# M401.net
KiCad netlist of a schematic drawn in EAGLE
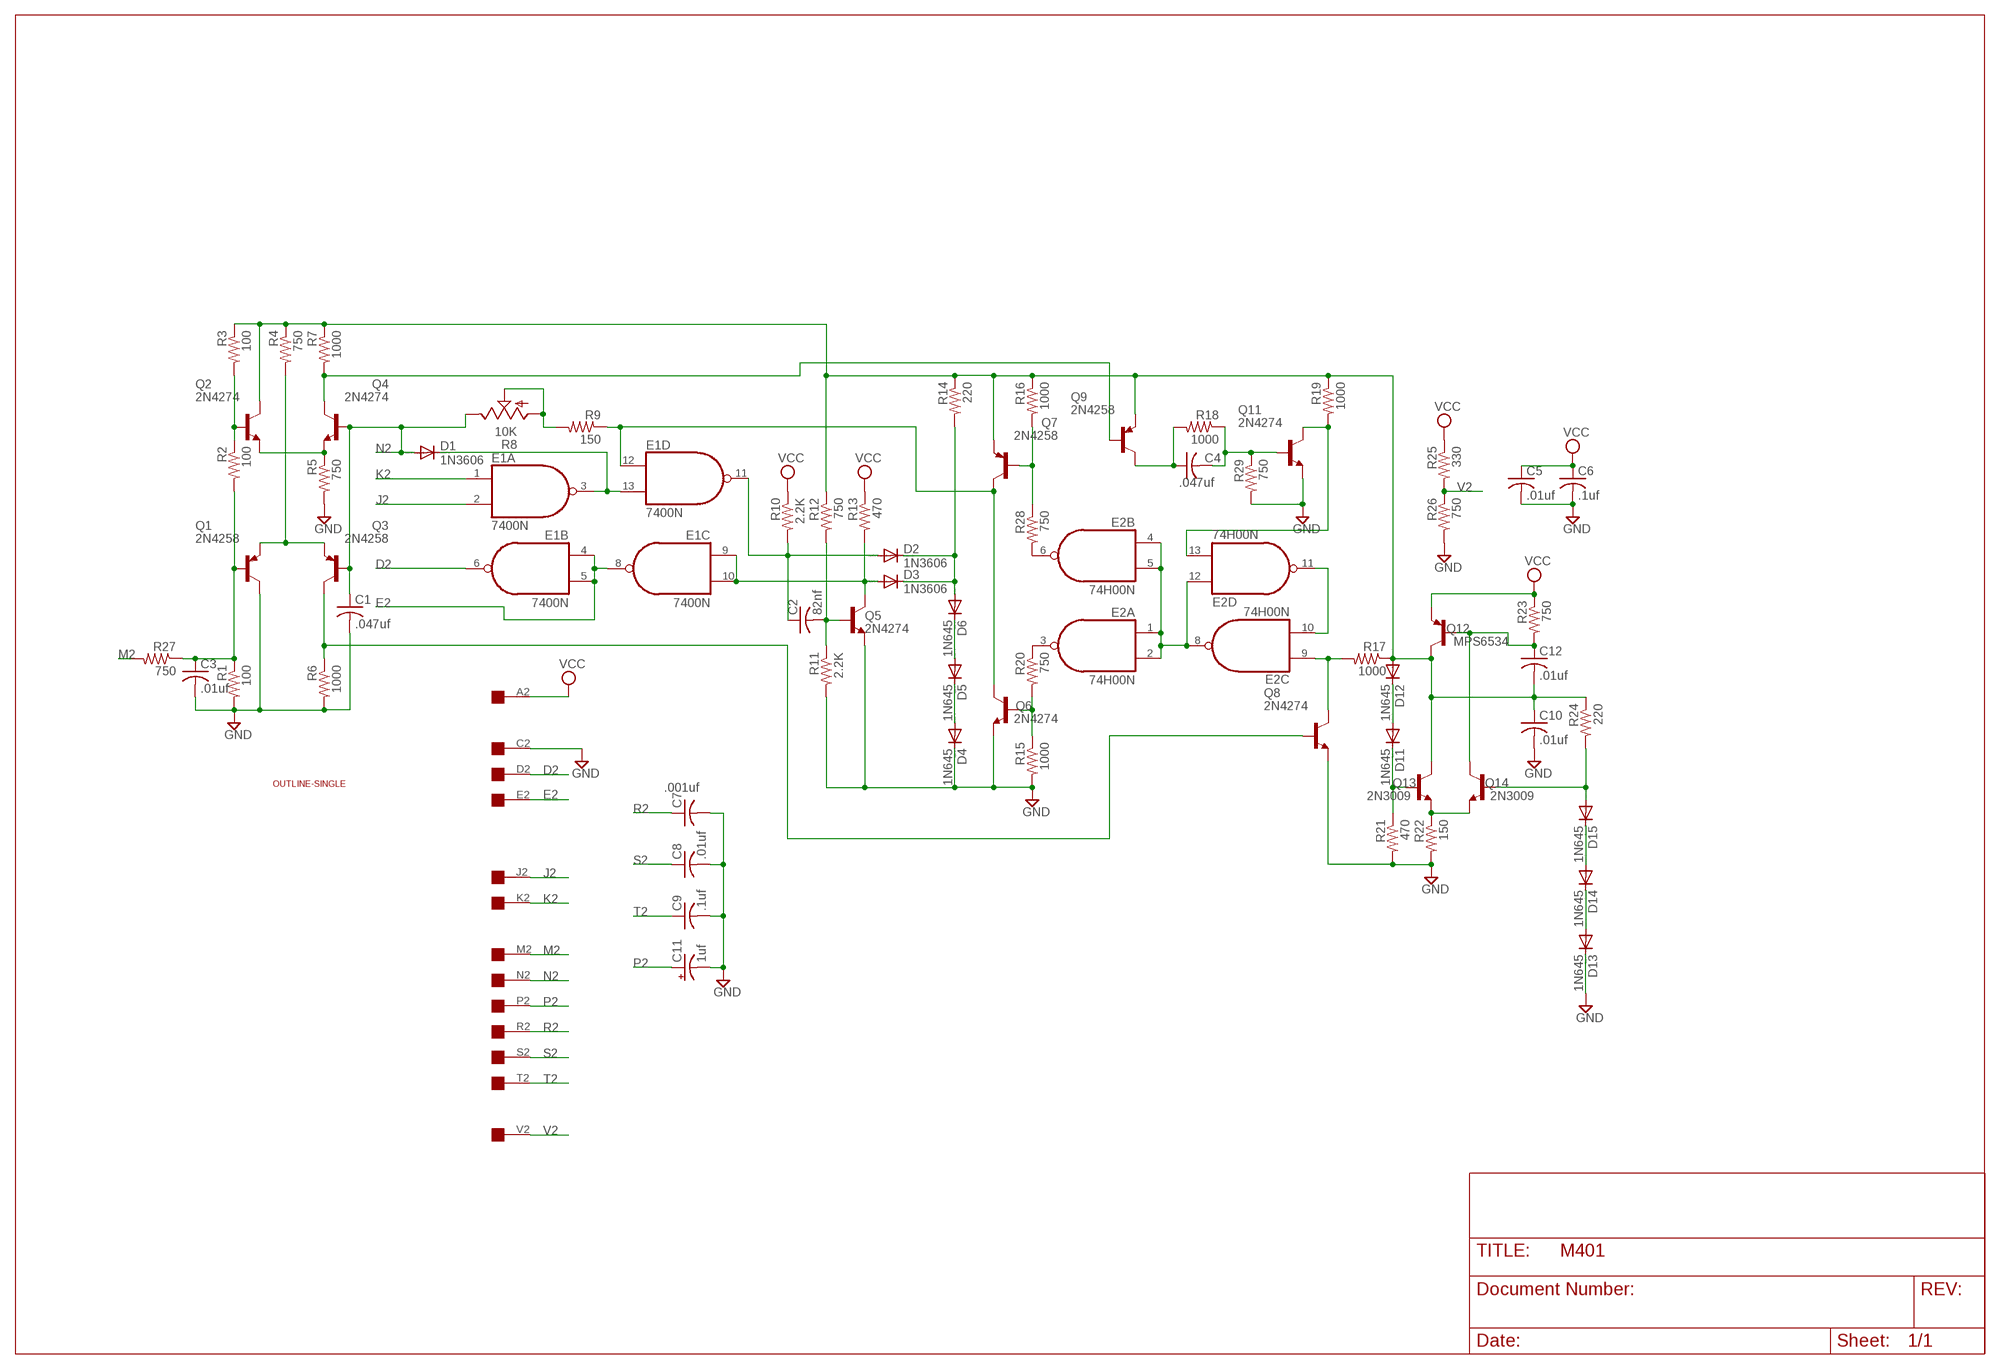
[diagram p0: schematic, sheet 1]

(export (version "E")
  (design (tool "Eeschema 10.0.6"))
  (components
    (comp (ref "C1")
      (value ".047uf")
      (footprint "eagle-import:C050-025X075")
      (libsource (lib "eagle-import") (part "C-US050-025X075"))
    )
    (comp (ref "C2")
      (value "82nf")
      (footprint "eagle-import:C050-025X075")
      (libsource (lib "eagle-import") (part "C-US050-025X075"))
    )
    (comp (ref "C3")
      (value ".01uf")
      (footprint "eagle-import:C050-025X075")
      (libsource (lib "eagle-import") (part "C-US050-025X075"))
    )
    (comp (ref "C4")
      (value ".047uf")
      (footprint "eagle-import:C050-025X075")
      (libsource (lib "eagle-import") (part "C-US050-025X075"))
    )
    (comp (ref "C5")
      (value ".01uf")
      (footprint "eagle-import:C050-025X075")
      (libsource (lib "eagle-import") (part "C-US050-025X075"))
    )
    (comp (ref "C6")
      (value ".1uf")
      (footprint "eagle-import:C050-025X075")
      (libsource (lib "eagle-import") (part "C-US050-025X075"))
    )
    (comp (ref "C7")
      (value ".001uf")
      (footprint "eagle-import:C050-025X075")
      (libsource (lib "eagle-import") (part "C-US050-025X075"))
    )
    (comp (ref "C8")
      (value ".01uf")
      (footprint "eagle-import:C050-025X075")
      (libsource (lib "eagle-import") (part "C-US050-025X075"))
    )
    (comp (ref "C9")
      (value ".1uf")
      (footprint "eagle-import:C050-025X075")
      (libsource (lib "eagle-import") (part "C-US050-025X075"))
    )
    (comp (ref "C10")
      (value ".01uf")
      (footprint "eagle-import:C050-025X075")
      (libsource (lib "eagle-import") (part "C-US050-025X075"))
    )
    (comp (ref "C11")
      (value "1uf")
      (footprint "eagle-import:E15-5")
      (libsource (lib "eagle-import") (part "CPOL-USE15-5AXIAL"))
    )
    (comp (ref "C12")
      (value ".01uf")
      (footprint "eagle-import:C050-025X075")
      (libsource (lib "eagle-import") (part "C-US050-025X075"))
    )
    (comp (ref "D1")
      (value "1N3606")
      (footprint "eagle-import:DO35-10")
      (libsource (lib "eagle-import") (part "1N4148DO35-10"))
    )
    (comp (ref "D2")
      (value "1N3606")
      (footprint "eagle-import:DO35-10")
      (libsource (lib "eagle-import") (part "1N4148DO35-10"))
    )
    (comp (ref "D3")
      (value "1N3606")
      (footprint "eagle-import:DO35-10")
      (libsource (lib "eagle-import") (part "1N4148DO35-10"))
    )
    (comp (ref "D4")
      (value "1N645")
      (footprint "eagle-import:DO35-10")
      (libsource (lib "eagle-import") (part "1N4148DO35-10"))
    )
    (comp (ref "D5")
      (value "1N645")
      (footprint "eagle-import:DO35-10")
      (libsource (lib "eagle-import") (part "1N4148DO35-10"))
    )
    (comp (ref "D6")
      (value "1N645")
      (footprint "eagle-import:DO35-10")
      (libsource (lib "eagle-import") (part "1N4148DO35-10"))
    )
    (comp (ref "D11")
      (value "1N645")
      (footprint "eagle-import:DO35-10")
      (libsource (lib "eagle-import") (part "1N4148DO35-10"))
    )
    (comp (ref "D12")
      (value "1N645")
      (footprint "eagle-import:DO35-10")
      (libsource (lib "eagle-import") (part "1N4148DO35-10"))
    )
    (comp (ref "D13")
      (value "1N645")
      (footprint "eagle-import:DO35-10")
      (libsource (lib "eagle-import") (part "1N4148DO35-10"))
    )
    (comp (ref "D14")
      (value "1N645")
      (footprint "eagle-import:DO35-10")
      (libsource (lib "eagle-import") (part "1N4148DO35-10"))
    )
    (comp (ref "D15")
      (value "1N645")
      (footprint "eagle-import:DO35-10")
      (libsource (lib "eagle-import") (part "1N4148DO35-10"))
    )
    (comp (ref "E1")
      (value "7400N")
      (footprint "eagle-import:DIL14")
      (libsource (lib "eagle-import") (part "7400N"))
    )
    (comp (ref "E2")
      (value "74H00N")
      (footprint "eagle-import:DIL14")
      (libsource (lib "eagle-import") (part "7400N"))
    )
    (comp (ref "Q1")
      (value "2N4258")
      (footprint "eagle-import:TO39")
      (libsource (lib "eagle-import") (part "-PNP-TO39-EBC2N3637"))
    )
    (comp (ref "Q2")
      (value "2N4274")
      (footprint "eagle-import:TO39")
      (libsource (lib "eagle-import") (part "-NPN-TO39-EBC2N3019"))
    )
    (comp (ref "Q3")
      (value "2N4258")
      (footprint "eagle-import:TO39")
      (libsource (lib "eagle-import") (part "-PNP-TO39-EBC2N3637"))
    )
    (comp (ref "Q4")
      (value "2N4274")
      (footprint "eagle-import:TO39")
      (libsource (lib "eagle-import") (part "-NPN-TO39-EBC2N3019"))
    )
    (comp (ref "Q5")
      (value "2N4274")
      (footprint "eagle-import:TO39")
      (libsource (lib "eagle-import") (part "-NPN-TO39-EBC2N3019"))
    )
    (comp (ref "Q6")
      (value "2N4274")
      (footprint "eagle-import:TO39")
      (libsource (lib "eagle-import") (part "-NPN-TO39-EBC2N3019"))
    )
    (comp (ref "Q7")
      (value "2N4258")
      (footprint "eagle-import:TO39")
      (libsource (lib "eagle-import") (part "-PNP-TO39-EBC2N3637"))
    )
    (comp (ref "Q8")
      (value "2N4274")
      (footprint "eagle-import:TO39")
      (libsource (lib "eagle-import") (part "-NPN-TO39-EBC2N3019"))
    )
    (comp (ref "Q9")
      (value "2N4258")
      (footprint "eagle-import:TO39")
      (libsource (lib "eagle-import") (part "-PNP-TO39-EBC2N3637"))
    )
    (comp (ref "Q11")
      (value "2N4274")
      (footprint "eagle-import:TO39")
      (libsource (lib "eagle-import") (part "-NPN-TO39-EBC2N3019"))
    )
    (comp (ref "Q12")
      (value "MPS6534")
      (footprint "eagle-import:TO39")
      (libsource (lib "eagle-import") (part "-PNP-TO39-EBC2N3637"))
    )
    (comp (ref "Q13")
      (value "2N3009")
      (footprint "eagle-import:TO39")
      (libsource (lib "eagle-import") (part "-NPN-TO39-EBC2N3019"))
    )
    (comp (ref "Q14")
      (value "2N3009")
      (footprint "eagle-import:TO39")
      (libsource (lib "eagle-import") (part "-NPN-TO39-EBC2N3019"))
    )
    (comp (ref "R1")
      (value "100")
      (footprint "eagle-import:0207_10")
      (libsource (lib "eagle-import") (part "R-US_0207/10"))
    )
    (comp (ref "R2")
      (value "100")
      (footprint "eagle-import:0207_10")
      (libsource (lib "eagle-import") (part "R-US_0207/10"))
    )
    (comp (ref "R3")
      (value "100")
      (footprint "eagle-import:0207_10")
      (libsource (lib "eagle-import") (part "R-US_0207/10"))
    )
    (comp (ref "R4")
      (value "750")
      (footprint "eagle-import:0207_10")
      (libsource (lib "eagle-import") (part "R-US_0207/10"))
    )
    (comp (ref "R5")
      (value "750")
      (footprint "eagle-import:0207_10")
      (libsource (lib "eagle-import") (part "R-US_0207/10"))
    )
    (comp (ref "R6")
      (value "1000")
      (footprint "eagle-import:0207_10")
      (libsource (lib "eagle-import") (part "R-US_0207/10"))
    )
    (comp (ref "R7")
      (value "1000")
      (footprint "eagle-import:0207_10")
      (libsource (lib "eagle-import") (part "R-US_0207/10"))
    )
    (comp (ref "R8")
      (value "10K")
      (footprint "eagle-import:PT-SPIN")
      (libsource (lib "eagle-import") (part "TRIM_US-PTSPIN"))
    )
    (comp (ref "R9")
      (value "150")
      (footprint "eagle-import:0207_10")
      (libsource (lib "eagle-import") (part "R-US_0207/10"))
    )
    (comp (ref "R10")
      (value "2.2K")
      (footprint "eagle-import:0207_10")
      (libsource (lib "eagle-import") (part "R-US_0207/10"))
    )
    (comp (ref "R11")
      (value "2.2K")
      (footprint "eagle-import:0207_10")
      (libsource (lib "eagle-import") (part "R-US_0207/10"))
    )
    (comp (ref "R12")
      (value "750")
      (footprint "eagle-import:0207_10")
      (libsource (lib "eagle-import") (part "R-US_0207/10"))
    )
    (comp (ref "R13")
      (value "470")
      (footprint "eagle-import:0207_10")
      (libsource (lib "eagle-import") (part "R-US_0207/10"))
    )
    (comp (ref "R14")
      (value "220")
      (footprint "eagle-import:0207_10")
      (libsource (lib "eagle-import") (part "R-US_0207/10"))
    )
    (comp (ref "R15")
      (value "1000")
      (footprint "eagle-import:0207_10")
      (libsource (lib "eagle-import") (part "R-US_0207/10"))
    )
    (comp (ref "R16")
      (value "1000")
      (footprint "eagle-import:0207_10")
      (libsource (lib "eagle-import") (part "R-US_0207/10"))
    )
    (comp (ref "R17")
      (value "1000")
      (footprint "eagle-import:0207_10")
      (libsource (lib "eagle-import") (part "R-US_0207/10"))
    )
    (comp (ref "R18")
      (value "1000")
      (footprint "eagle-import:0207_10")
      (libsource (lib "eagle-import") (part "R-US_0207/10"))
    )
    (comp (ref "R19")
      (value "1000")
      (footprint "eagle-import:0207_10")
      (libsource (lib "eagle-import") (part "R-US_0207/10"))
    )
    (comp (ref "R20")
      (value "750")
      (footprint "eagle-import:0207_10")
      (libsource (lib "eagle-import") (part "R-US_0207/10"))
    )
    (comp (ref "R21")
      (value "470")
      (footprint "eagle-import:0207_10")
      (libsource (lib "eagle-import") (part "R-US_0207/10"))
    )
    (comp (ref "R22")
      (value "150")
      (footprint "eagle-import:0207_10")
      (libsource (lib "eagle-import") (part "R-US_0207/10"))
    )
    (comp (ref "R23")
      (value "750")
      (footprint "eagle-import:0207_10")
      (libsource (lib "eagle-import") (part "R-US_0207/10"))
    )
    (comp (ref "R24")
      (value "220")
      (footprint "eagle-import:0207_10")
      (libsource (lib "eagle-import") (part "R-US_0207/10"))
    )
    (comp (ref "R25")
      (value "330")
      (footprint "eagle-import:0207_10")
      (libsource (lib "eagle-import") (part "R-US_0207/10"))
    )
    (comp (ref "R26")
      (value "750")
      (footprint "eagle-import:0207_10")
      (libsource (lib "eagle-import") (part "R-US_0207/10"))
    )
    (comp (ref "R27")
      (value "750")
      (footprint "eagle-import:0207_10")
      (libsource (lib "eagle-import") (part "R-US_0207/10"))
    )
    (comp (ref "R28")
      (value "750")
      (footprint "eagle-import:0207_10")
      (libsource (lib "eagle-import") (part "R-US_0207/10"))
    )
    (comp (ref "R29")
      (value "750")
      (footprint "eagle-import:0207_10")
      (libsource (lib "eagle-import") (part "R-US_0207/10"))
    )
    (comp (ref "U$1")
      (value "OUTLINE-SINGLE")
      (footprint "eagle-import:SINGLE")
      (libsource (lib "eagle-import") (part "OUTLINE-SINGLE"))
    )
    (comp (ref "U$2")
      (value "EDGE-1")
      (footprint "eagle-import:EDGE-CON1")
      (libsource (lib "eagle-import") (part "EDGE-1"))
    )
  )
  (nets
    (net (code "1") (name "/D2") (class "Default")
      (node (ref "E1") (pin "6") (pinfunction "O_6") (pintype "output"))
      (node (ref "U$2") (pin "D2") (pinfunction "1_D2") (pintype "bidirectional"))
    )
    (net (code "2") (name "/E2") (class "Default")
      (node (ref "E1") (pin "4") (pinfunction "I0_4") (pintype "input"))
      (node (ref "E1") (pin "5") (pinfunction "I1_5") (pintype "input"))
      (node (ref "E1") (pin "8") (pinfunction "O_8") (pintype "output"))
      (node (ref "U$2") (pin "E2") (pinfunction "1_E2") (pintype "bidirectional"))
    )
    (net (code "3") (name "/J2") (class "Default")
      (node (ref "E1") (pin "2") (pinfunction "I1_2") (pintype "input"))
      (node (ref "U$2") (pin "J2") (pinfunction "1_J2") (pintype "bidirectional"))
    )
    (net (code "4") (name "/K2") (class "Default")
      (node (ref "E1") (pin "1") (pinfunction "I0_1") (pintype "input"))
      (node (ref "U$2") (pin "K2") (pinfunction "1_K2") (pintype "bidirectional"))
    )
    (net (code "5") (name "/M2") (class "Default")
      (node (ref "R27") (pin "2") (pinfunction "2_2") (pintype "passive"))
      (node (ref "U$2") (pin "M2") (pinfunction "1_M2") (pintype "bidirectional"))
    )
    (net (code "6") (name "/N2") (class "Default")
      (node (ref "C1") (pin "1") (pinfunction "1_1") (pintype "passive"))
      (node (ref "D1") (pin "A") (pinfunction "A_A") (pintype "passive"))
      (node (ref "Q3") (pin "2") (pinfunction "B_2") (pintype "passive"))
      (node (ref "Q4") (pin "2") (pinfunction "B_2") (pintype "passive"))
      (node (ref "R8") (pin "E") (pinfunction "E_E") (pintype "passive"))
      (node (ref "U$2") (pin "N2") (pinfunction "1_N2") (pintype "bidirectional"))
    )
    (net (code "7") (name "/P2") (class "Default")
      (node (ref "C11") (pin "+") (pinfunction "+_+") (pintype "passive"))
      (node (ref "U$2") (pin "P2") (pinfunction "1_P2") (pintype "bidirectional"))
    )
    (net (code "8") (name "/R2") (class "Default")
      (node (ref "C7") (pin "1") (pinfunction "1_1") (pintype "passive"))
      (node (ref "U$2") (pin "R2") (pinfunction "1_R2") (pintype "bidirectional"))
    )
    (net (code "9") (name "/S2") (class "Default")
      (node (ref "C8") (pin "1") (pinfunction "1_1") (pintype "passive"))
      (node (ref "U$2") (pin "S2") (pinfunction "1_S2") (pintype "bidirectional"))
    )
    (net (code "10") (name "/T2") (class "Default")
      (node (ref "C9") (pin "1") (pinfunction "1_1") (pintype "passive"))
      (node (ref "U$2") (pin "T2") (pinfunction "1_T2") (pintype "bidirectional"))
    )
    (net (code "11") (name "/V2") (class "Default")
      (node (ref "R25") (pin "2") (pinfunction "2_2") (pintype "passive"))
      (node (ref "R26") (pin "1") (pinfunction "1_1") (pintype "passive"))
      (node (ref "U$2") (pin "V2") (pinfunction "1_V2") (pintype "bidirectional"))
    )
    (net (code "12") (name "GND") (class "Default")
      (node (ref "C1") (pin "2") (pinfunction "2_2") (pintype "passive"))
      (node (ref "C10") (pin "2") (pinfunction "2_2") (pintype "passive"))
      (node (ref "C11") (pin "-") (pinfunction "-_-") (pintype "passive"))
      (node (ref "C3") (pin "2") (pinfunction "2_2") (pintype "passive"))
      (node (ref "C5") (pin "2") (pinfunction "2_2") (pintype "passive"))
      (node (ref "C6") (pin "2") (pinfunction "2_2") (pintype "passive"))
      (node (ref "C7") (pin "2") (pinfunction "2_2") (pintype "passive"))
      (node (ref "C8") (pin "2") (pinfunction "2_2") (pintype "passive"))
      (node (ref "C9") (pin "2") (pinfunction "2_2") (pintype "passive"))
      (node (ref "D13") (pin "C") (pinfunction "C_C") (pintype "passive"))
      (node (ref "D4") (pin "C") (pinfunction "C_C") (pintype "passive"))
      (node (ref "Q1") (pin "3") (pinfunction "C_3") (pintype "passive"))
      (node (ref "Q11") (pin "1") (pinfunction "E_1") (pintype "passive"))
      (node (ref "Q5") (pin "1") (pinfunction "E_1") (pintype "passive"))
      (node (ref "Q6") (pin "1") (pinfunction "E_1") (pintype "passive"))
      (node (ref "Q8") (pin "1") (pinfunction "E_1") (pintype "passive"))
      (node (ref "R1") (pin "2") (pinfunction "2_2") (pintype "passive"))
      (node (ref "R11") (pin "2") (pinfunction "2_2") (pintype "passive"))
      (node (ref "R15") (pin "2") (pinfunction "2_2") (pintype "passive"))
      (node (ref "R21") (pin "2") (pinfunction "2_2") (pintype "passive"))
      (node (ref "R22") (pin "2") (pinfunction "2_2") (pintype "passive"))
      (node (ref "R26") (pin "2") (pinfunction "2_2") (pintype "passive"))
      (node (ref "R29") (pin "2") (pinfunction "2_2") (pintype "passive"))
      (node (ref "R5") (pin "2") (pinfunction "2_2") (pintype "passive"))
      (node (ref "R6") (pin "2") (pinfunction "2_2") (pintype "passive"))
      (node (ref "U$2") (pin "C2") (pinfunction "1_C2") (pintype "bidirectional"))
    )
    (net (code "13") (name "Net-(D2-PadC)") (class "Default")
      (node (ref "D2") (pin "C") (pinfunction "C_C") (pintype "passive"))
      (node (ref "D3") (pin "C") (pinfunction "C_C") (pintype "passive"))
      (node (ref "D6") (pin "A") (pinfunction "A_A") (pintype "passive"))
      (node (ref "R14") (pin "2") (pinfunction "2_2") (pintype "passive"))
    )
    (net (code "14") (name "Net-(D4-PadA)") (class "Default")
      (node (ref "D4") (pin "A") (pinfunction "A_A") (pintype "passive"))
      (node (ref "D5") (pin "C") (pinfunction "C_C") (pintype "passive"))
    )
    (net (code "15") (name "Net-(D5-PadA)") (class "Default")
      (node (ref "D5") (pin "A") (pinfunction "A_A") (pintype "passive"))
      (node (ref "D6") (pin "C") (pinfunction "C_C") (pintype "passive"))
    )
    (net (code "16") (name "Net-(D11-PadA)") (class "Default")
      (node (ref "D11") (pin "A") (pinfunction "A_A") (pintype "passive"))
      (node (ref "D12") (pin "C") (pinfunction "C_C") (pintype "passive"))
    )
    (net (code "17") (name "Net-(D13-PadA)") (class "Default")
      (node (ref "D13") (pin "A") (pinfunction "A_A") (pintype "passive"))
      (node (ref "D14") (pin "C") (pinfunction "C_C") (pintype "passive"))
    )
    (net (code "18") (name "Net-(D14-PadA)") (class "Default")
      (node (ref "D14") (pin "A") (pinfunction "A_A") (pintype "passive"))
      (node (ref "D15") (pin "C") (pinfunction "C_C") (pintype "passive"))
    )
    (net (code "19") (name "Net-(E1A-O)") (class "Default")
      (node (ref "D1") (pin "C") (pinfunction "C_C") (pintype "passive"))
      (node (ref "E1") (pin "13") (pinfunction "I1_13") (pintype "input"))
      (node (ref "E1") (pin "3") (pinfunction "O_3") (pintype "output"))
    )
    (net (code "20") (name "Net-(E1C-I0)") (class "Default")
      (node (ref "D3") (pin "A") (pinfunction "A_A") (pintype "passive"))
      (node (ref "E1") (pin "10") (pinfunction "I1_10") (pintype "input"))
      (node (ref "E1") (pin "9") (pinfunction "I0_9") (pintype "input"))
      (node (ref "Q5") (pin "3") (pinfunction "C_3") (pintype "passive"))
      (node (ref "R13") (pin "2") (pinfunction "2_2") (pintype "passive"))
    )
    (net (code "21") (name "Net-(E1D-I0)") (class "Default")
      (node (ref "E1") (pin "12") (pinfunction "I0_12") (pintype "input"))
      (node (ref "Q6") (pin "3") (pinfunction "C_3") (pintype "passive"))
      (node (ref "Q7") (pin "3") (pinfunction "C_3") (pintype "passive"))
      (node (ref "R9") (pin "1") (pinfunction "1_1") (pintype "passive"))
    )
    (net (code "22") (name "Net-(E1D-O)") (class "Default")
      (node (ref "C2") (pin "1") (pinfunction "1_1") (pintype "passive"))
      (node (ref "D2") (pin "A") (pinfunction "A_A") (pintype "passive"))
      (node (ref "E1") (pin "11") (pinfunction "O_11") (pintype "output"))
      (node (ref "R10") (pin "2") (pinfunction "2_2") (pintype "passive"))
    )
    (net (code "23") (name "Net-(E2A-I0)") (class "Default")
      (node (ref "E2") (pin "1") (pinfunction "I0_1") (pintype "input"))
      (node (ref "E2") (pin "12") (pinfunction "I0_12") (pintype "input"))
      (node (ref "E2") (pin "2") (pinfunction "I1_2") (pintype "input"))
      (node (ref "E2") (pin "4") (pinfunction "I0_4") (pintype "input"))
      (node (ref "E2") (pin "5") (pinfunction "I1_5") (pintype "input"))
      (node (ref "E2") (pin "8") (pinfunction "O_8") (pintype "output"))
    )
    (net (code "24") (name "Net-(E2A-O)") (class "Default")
      (node (ref "E2") (pin "3") (pinfunction "O_3") (pintype "output"))
      (node (ref "R20") (pin "1") (pinfunction "1_1") (pintype "passive"))
    )
    (net (code "25") (name "Net-(E2B-O)") (class "Default")
      (node (ref "E2") (pin "6") (pinfunction "O_6") (pintype "output"))
      (node (ref "R28") (pin "2") (pinfunction "2_2") (pintype "passive"))
    )
    (net (code "26") (name "Net-(E2C-I0)") (class "Default")
      (node (ref "E2") (pin "9") (pinfunction "I0_9") (pintype "input"))
      (node (ref "Q8") (pin "3") (pinfunction "C_3") (pintype "passive"))
      (node (ref "R17") (pin "2") (pinfunction "2_2") (pintype "passive"))
    )
    (net (code "27") (name "Net-(E2C-I1)") (class "Default")
      (node (ref "E2") (pin "10") (pinfunction "I1_10") (pintype "input"))
      (node (ref "E2") (pin "11") (pinfunction "O_11") (pintype "output"))
    )
    (net (code "28") (name "Net-(E2D-I1)") (class "Default")
      (node (ref "E2") (pin "13") (pinfunction "I1_13") (pintype "input"))
      (node (ref "Q11") (pin "3") (pinfunction "C_3") (pintype "passive"))
      (node (ref "R19") (pin "2") (pinfunction "2_2") (pintype "passive"))
    )
    (net (code "29") (name "Net-(Q1-B)") (class "Default")
      (node (ref "C3") (pin "1") (pinfunction "1_1") (pintype "passive"))
      (node (ref "Q1") (pin "2") (pinfunction "B_2") (pintype "passive"))
      (node (ref "R1") (pin "1") (pinfunction "1_1") (pintype "passive"))
      (node (ref "R2") (pin "2") (pinfunction "2_2") (pintype "passive"))
      (node (ref "R27") (pin "1") (pinfunction "1_1") (pintype "passive"))
    )
    (net (code "30") (name "Net-(Q1-E)") (class "Default")
      (node (ref "Q1") (pin "1") (pinfunction "E_1") (pintype "passive"))
      (node (ref "Q3") (pin "1") (pinfunction "E_1") (pintype "passive"))
      (node (ref "R4") (pin "2") (pinfunction "2_2") (pintype "passive"))
    )
    (net (code "31") (name "Net-(Q2-B)") (class "Default")
      (node (ref "Q2") (pin "2") (pinfunction "B_2") (pintype "passive"))
      (node (ref "R2") (pin "1") (pinfunction "1_1") (pintype "passive"))
      (node (ref "R3") (pin "2") (pinfunction "2_2") (pintype "passive"))
    )
    (net (code "32") (name "Net-(Q2-E)") (class "Default")
      (node (ref "Q2") (pin "1") (pinfunction "E_1") (pintype "passive"))
      (node (ref "Q4") (pin "1") (pinfunction "E_1") (pintype "passive"))
      (node (ref "R5") (pin "1") (pinfunction "1_1") (pintype "passive"))
    )
    (net (code "33") (name "Net-(Q3-C)") (class "Default")
      (node (ref "Q3") (pin "3") (pinfunction "C_3") (pintype "passive"))
      (node (ref "Q8") (pin "2") (pinfunction "B_2") (pintype "passive"))
      (node (ref "R6") (pin "1") (pinfunction "1_1") (pintype "passive"))
    )
    (net (code "34") (name "Net-(Q4-C)") (class "Default")
      (node (ref "Q4") (pin "3") (pinfunction "C_3") (pintype "passive"))
      (node (ref "Q9") (pin "2") (pinfunction "B_2") (pintype "passive"))
      (node (ref "R7") (pin "2") (pinfunction "2_2") (pintype "passive"))
    )
    (net (code "35") (name "Net-(Q5-B)") (class "Default")
      (node (ref "C2") (pin "2") (pinfunction "2_2") (pintype "passive"))
      (node (ref "Q5") (pin "2") (pinfunction "B_2") (pintype "passive"))
      (node (ref "R11") (pin "1") (pinfunction "1_1") (pintype "passive"))
      (node (ref "R12") (pin "2") (pinfunction "2_2") (pintype "passive"))
    )
    (net (code "36") (name "Net-(Q6-B)") (class "Default")
      (node (ref "Q6") (pin "2") (pinfunction "B_2") (pintype "passive"))
      (node (ref "R15") (pin "1") (pinfunction "1_1") (pintype "passive"))
      (node (ref "R20") (pin "2") (pinfunction "2_2") (pintype "passive"))
    )
    (net (code "37") (name "Net-(Q7-B)") (class "Default")
      (node (ref "Q7") (pin "2") (pinfunction "B_2") (pintype "passive"))
      (node (ref "R16") (pin "2") (pinfunction "2_2") (pintype "passive"))
      (node (ref "R28") (pin "1") (pinfunction "1_1") (pintype "passive"))
    )
    (net (code "38") (name "Net-(Q9-C)") (class "Default")
      (node (ref "C4") (pin "1") (pinfunction "1_1") (pintype "passive"))
      (node (ref "Q9") (pin "3") (pinfunction "C_3") (pintype "passive"))
      (node (ref "R18") (pin "2") (pinfunction "2_2") (pintype "passive"))
    )
    (net (code "39") (name "Net-(Q11-B)") (class "Default")
      (node (ref "C4") (pin "2") (pinfunction "2_2") (pintype "passive"))
      (node (ref "Q11") (pin "2") (pinfunction "B_2") (pintype "passive"))
      (node (ref "R18") (pin "1") (pinfunction "1_1") (pintype "passive"))
      (node (ref "R29") (pin "1") (pinfunction "1_1") (pintype "passive"))
    )
    (net (code "40") (name "Net-(Q12-B)") (class "Default")
      (node (ref "C12") (pin "1") (pinfunction "1_1") (pintype "passive"))
      (node (ref "Q12") (pin "2") (pinfunction "B_2") (pintype "passive"))
      (node (ref "Q14") (pin "3") (pinfunction "C_3") (pintype "passive"))
      (node (ref "R23") (pin "2") (pinfunction "2_2") (pintype "passive"))
    )
    (net (code "41") (name "Net-(Q12-C)") (class "Default")
      (node (ref "C10") (pin "1") (pinfunction "1_1") (pintype "passive"))
      (node (ref "C12") (pin "2") (pinfunction "2_2") (pintype "passive"))
      (node (ref "D12") (pin "A") (pinfunction "A_A") (pintype "passive"))
      (node (ref "Q12") (pin "3") (pinfunction "C_3") (pintype "passive"))
      (node (ref "Q13") (pin "3") (pinfunction "C_3") (pintype "passive"))
      (node (ref "Q2") (pin "3") (pinfunction "C_3") (pintype "passive"))
      (node (ref "Q7") (pin "1") (pinfunction "E_1") (pintype "passive"))
      (node (ref "Q9") (pin "1") (pinfunction "E_1") (pintype "passive"))
      (node (ref "R12") (pin "1") (pinfunction "1_1") (pintype "passive"))
      (node (ref "R14") (pin "1") (pinfunction "1_1") (pintype "passive"))
      (node (ref "R16") (pin "1") (pinfunction "1_1") (pintype "passive"))
      (node (ref "R17") (pin "1") (pinfunction "1_1") (pintype "passive"))
      (node (ref "R19") (pin "1") (pinfunction "1_1") (pintype "passive"))
      (node (ref "R24") (pin "1") (pinfunction "1_1") (pintype "passive"))
      (node (ref "R3") (pin "1") (pinfunction "1_1") (pintype "passive"))
      (node (ref "R4") (pin "1") (pinfunction "1_1") (pintype "passive"))
      (node (ref "R7") (pin "1") (pinfunction "1_1") (pintype "passive"))
    )
    (net (code "42") (name "Net-(Q13-B)") (class "Default")
      (node (ref "D11") (pin "C") (pinfunction "C_C") (pintype "passive"))
      (node (ref "Q13") (pin "2") (pinfunction "B_2") (pintype "passive"))
      (node (ref "R21") (pin "1") (pinfunction "1_1") (pintype "passive"))
    )
    (net (code "43") (name "Net-(Q13-E)") (class "Default")
      (node (ref "Q13") (pin "1") (pinfunction "E_1") (pintype "passive"))
      (node (ref "Q14") (pin "1") (pinfunction "E_1") (pintype "passive"))
      (node (ref "R22") (pin "1") (pinfunction "1_1") (pintype "passive"))
    )
    (net (code "44") (name "Net-(Q14-B)") (class "Default")
      (node (ref "D15") (pin "A") (pinfunction "A_A") (pintype "passive"))
      (node (ref "Q14") (pin "2") (pinfunction "B_2") (pintype "passive"))
      (node (ref "R24") (pin "2") (pinfunction "2_2") (pintype "passive"))
    )
    (net (code "45") (name "Net-(R8-PadA)") (class "Default")
      (node (ref "R8") (pin "A") (pinfunction "A_A") (pintype "passive"))
      (node (ref "R8") (pin "S") (pinfunction "S_S") (pintype "passive"))
      (node (ref "R9") (pin "2") (pinfunction "2_2") (pintype "passive"))
    )
    (net (code "46") (name "VCC") (class "Default")
      (node (ref "C5") (pin "1") (pinfunction "1_1") (pintype "passive"))
      (node (ref "C6") (pin "1") (pinfunction "1_1") (pintype "passive"))
      (node (ref "Q12") (pin "1") (pinfunction "E_1") (pintype "passive"))
      (node (ref "R10") (pin "1") (pinfunction "1_1") (pintype "passive"))
      (node (ref "R13") (pin "1") (pinfunction "1_1") (pintype "passive"))
      (node (ref "R23") (pin "1") (pinfunction "1_1") (pintype "passive"))
      (node (ref "R25") (pin "1") (pinfunction "1_1") (pintype "passive"))
      (node (ref "U$2") (pin "A2") (pinfunction "1_A2") (pintype "bidirectional"))
    )
  )
)
